# V0_8.net
KiCad netlist of a schematic drawn in EAGLE
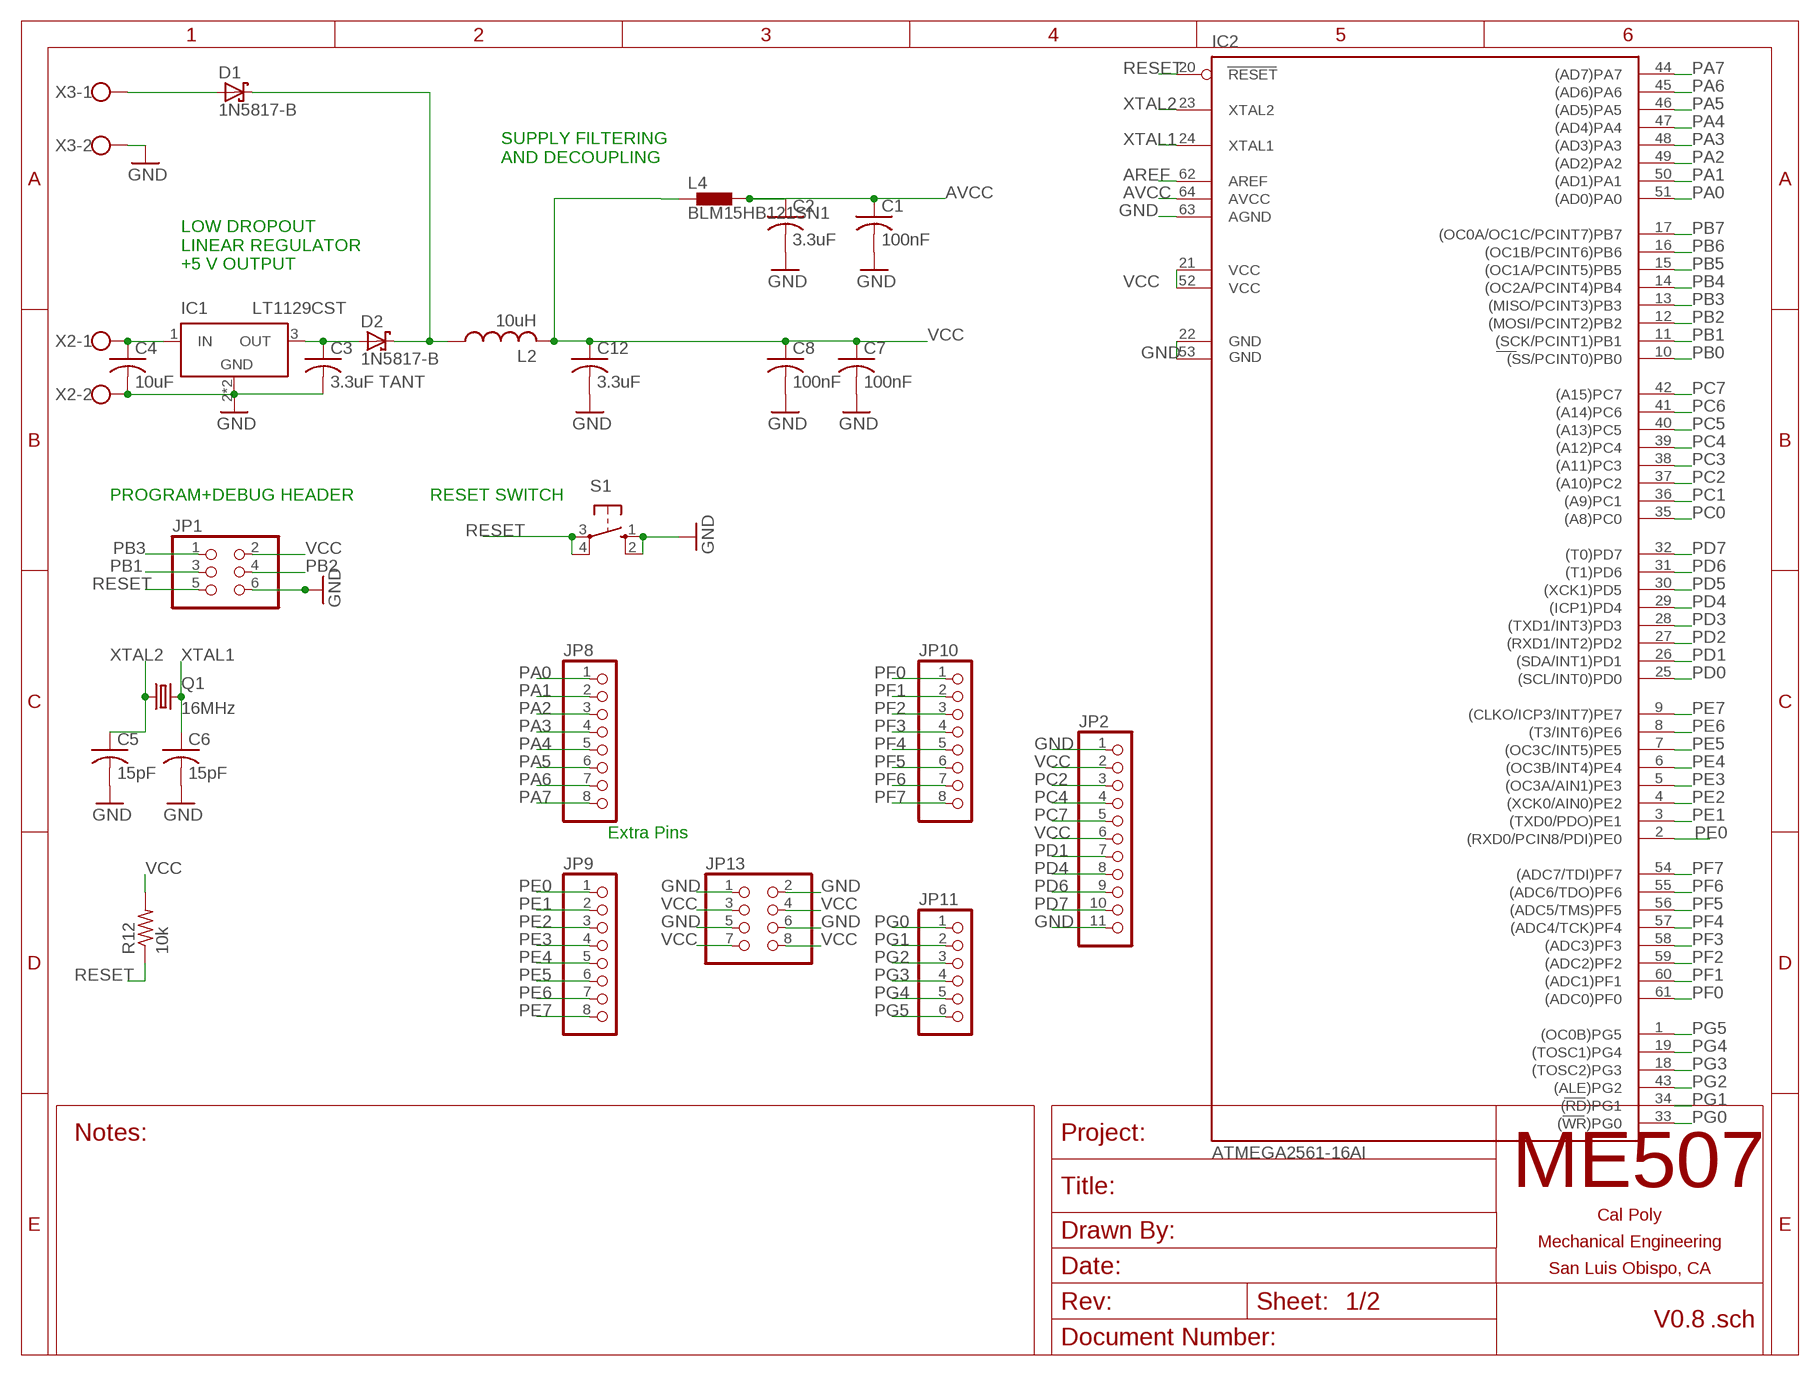
[diagram p0: schematic, sheet 1]
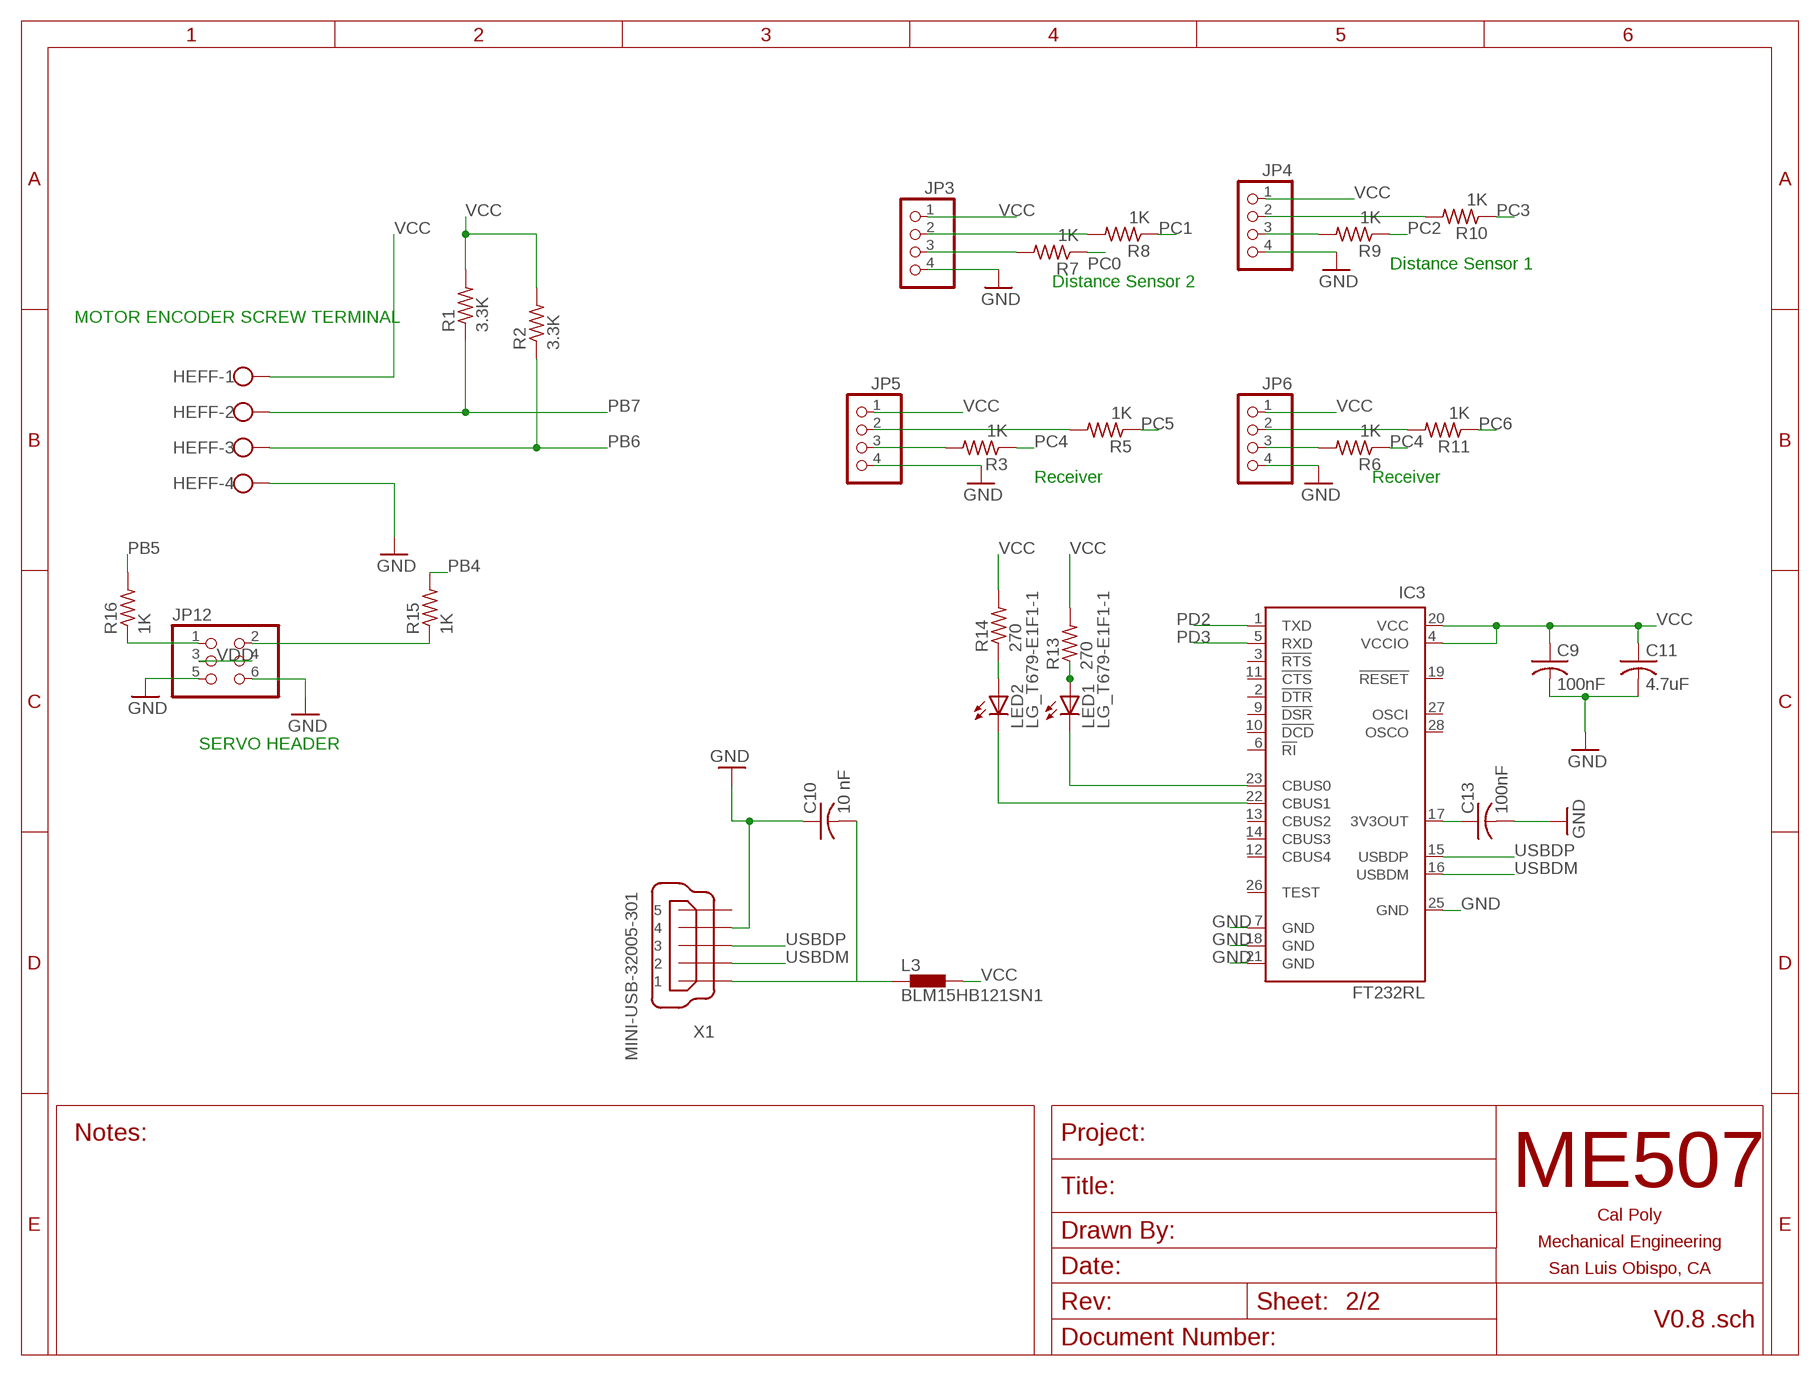
[diagram p1: schematic, sheet 2]

(export (version "E")
  (design (tool "Eeschema 10.0.6"))
  (components
    (comp (ref "C9")
      (value "100nF")
      (footprint "eagle-import:C0805")
      (libsource (lib "eagle-import") (part "C-USC0805"))
    )
    (comp (ref "C10")
      (value "10 nF")
      (footprint "eagle-import:C0805")
      (libsource (lib "eagle-import") (part "C-USC0805"))
    )
    (comp (ref "C11")
      (value "4.7uF")
      (footprint "eagle-import:C0805")
      (libsource (lib "eagle-import") (part "C-USC0805"))
    )
    (comp (ref "C13")
      (value "100nF")
      (footprint "eagle-import:C0805")
      (libsource (lib "eagle-import") (part "C-USC0805"))
    )
    (comp (ref "HEFF")
      (value "W237-4")
      (footprint "eagle-import:W237-4")
      (libsource (lib "eagle-import") (part "W237-4"))
    )
    (comp (ref "IC3")
      (value "FT232RL")
      (footprint "eagle-import:SSOP28")
      (libsource (lib "eagle-import") (part "FT232RL"))
    )
    (comp (ref "JP3")
      (value "PINHD-1X4")
      (footprint "eagle-import:1X04")
      (libsource (lib "eagle-import") (part "PINHD-1X4"))
    )
    (comp (ref "JP4")
      (value "PINHD-1X4")
      (footprint "eagle-import:1X04")
      (libsource (lib "eagle-import") (part "PINHD-1X4"))
    )
    (comp (ref "JP5")
      (value "PINHD-1X4")
      (footprint "eagle-import:1X04")
      (libsource (lib "eagle-import") (part "PINHD-1X4"))
    )
    (comp (ref "JP6")
      (value "PINHD-1X4")
      (footprint "eagle-import:1X04")
      (libsource (lib "eagle-import") (part "PINHD-1X4"))
    )
    (comp (ref "JP12")
      (value "PINHD-2X3")
      (footprint "eagle-import:2X03")
      (libsource (lib "eagle-import") (part "PINHD-2X3"))
    )
    (comp (ref "L3")
      (value "BLM15HB121SN1")
      (footprint "eagle-import:0402")
      (libsource (lib "eagle-import") (part "BLM15HB121SN1"))
    )
    (comp (ref "LED1")
      (value "LG_T679-E1F1-1")
      (footprint "eagle-import:PLCC2")
      (libsource (lib "eagle-import") (part "_T679-?-1E1F1LG"))
    )
    (comp (ref "LED2")
      (value "LG_T679-E1F1-1")
      (footprint "eagle-import:PLCC2")
      (libsource (lib "eagle-import") (part "_T679-?-1E1F1LG"))
    )
    (comp (ref "R1")
      (value "3.3K")
      (footprint "eagle-import:R0805")
      (libsource (lib "eagle-import") (part "R-US_R0805"))
    )
    (comp (ref "R2")
      (value "3.3K")
      (footprint "eagle-import:R0805")
      (libsource (lib "eagle-import") (part "R-US_R0805"))
    )
    (comp (ref "R3")
      (value "1K")
      (footprint "eagle-import:R0805")
      (libsource (lib "eagle-import") (part "R-US_R0805"))
    )
    (comp (ref "R5")
      (value "1K")
      (footprint "eagle-import:R0805")
      (libsource (lib "eagle-import") (part "R-US_R0805"))
    )
    (comp (ref "R6")
      (value "1K")
      (footprint "eagle-import:R0805")
      (libsource (lib "eagle-import") (part "R-US_R0805"))
    )
    (comp (ref "R7")
      (value "1K")
      (footprint "eagle-import:R0805")
      (libsource (lib "eagle-import") (part "R-US_R0805"))
    )
    (comp (ref "R8")
      (value "1K")
      (footprint "eagle-import:R0805")
      (libsource (lib "eagle-import") (part "R-US_R0805"))
    )
    (comp (ref "R9")
      (value "1K")
      (footprint "eagle-import:R0805")
      (libsource (lib "eagle-import") (part "R-US_R0805"))
    )
    (comp (ref "R10")
      (value "1K")
      (footprint "eagle-import:R0805")
      (libsource (lib "eagle-import") (part "R-US_R0805"))
    )
    (comp (ref "R11")
      (value "1K")
      (footprint "eagle-import:R0805")
      (libsource (lib "eagle-import") (part "R-US_R0805"))
    )
    (comp (ref "R13")
      (value "270")
      (footprint "eagle-import:R0805")
      (libsource (lib "eagle-import") (part "R-US_R0805"))
    )
    (comp (ref "R14")
      (value "270")
      (footprint "eagle-import:R0805")
      (libsource (lib "eagle-import") (part "R-US_R0805"))
    )
    (comp (ref "R15")
      (value "1K")
      (footprint "eagle-import:R0805")
      (libsource (lib "eagle-import") (part "R-US_R0805"))
    )
    (comp (ref "R16")
      (value "1K")
      (footprint "eagle-import:R0805")
      (libsource (lib "eagle-import") (part "R-US_R0805"))
    )
    (comp (ref "X1")
      (value "MINI-USB-32005-301")
      (footprint "eagle-import:32005-301")
      (libsource (lib "eagle-import") (part "MINI-USB-32005-301"))
    )
    (comp (ref "C1")
      (value "100nF")
      (footprint "eagle-import:C0805")
      (libsource (lib "eagle-import") (part "C-USC0805"))
    )
    (comp (ref "C2")
      (value "3.3uF")
      (footprint "eagle-import:C0805")
      (libsource (lib "eagle-import") (part "C-USC0805"))
    )
    (comp (ref "C3")
      (value "3.3uF TANT")
      (footprint "eagle-import:C0805")
      (libsource (lib "eagle-import") (part "C-USC0805"))
    )
    (comp (ref "C4")
      (value "10uF")
      (footprint "eagle-import:C0805")
      (libsource (lib "eagle-import") (part "C-USC0805"))
    )
    (comp (ref "C5")
      (value "15pF")
      (footprint "eagle-import:C0805")
      (libsource (lib "eagle-import") (part "C-USC0805"))
    )
    (comp (ref "C6")
      (value "15pF")
      (footprint "eagle-import:C0805")
      (libsource (lib "eagle-import") (part "C-USC0805"))
    )
    (comp (ref "C7")
      (value "100nF")
      (footprint "eagle-import:C0805")
      (libsource (lib "eagle-import") (part "C-USC0805"))
    )
    (comp (ref "C8")
      (value "100nF")
      (footprint "eagle-import:C0805")
      (libsource (lib "eagle-import") (part "C-USC0805"))
    )
    (comp (ref "C12")
      (value "3.3uF")
      (footprint "eagle-import:C0805")
      (libsource (lib "eagle-import") (part "C-USC0805"))
    )
    (comp (ref "D1")
      (value "1N5817-B")
      (footprint "eagle-import:DO41-7.6")
      (libsource (lib "eagle-import") (part "1N5817-B"))
    )
    (comp (ref "D2")
      (value "1N5817-B")
      (footprint "eagle-import:DO41-7.6")
      (libsource (lib "eagle-import") (part "1N5817-B"))
    )
    (comp (ref "IC1")
      (value "LT1129CST")
      (footprint "eagle-import:SOT223")
      (fields (field (name "MPN") "LT1129CST-5#PBF"))
      (libsource (lib "eagle-import") (part "LT1129CST"))
    )
    (comp (ref "IC2")
      (value "ATMEGA2561-16AI")
      (footprint "eagle-import:TQFP64")
      (libsource (lib "eagle-import") (part "ATMEGA2561AI-16"))
    )
    (comp (ref "JP1")
      (value "PINHD-2X3")
      (footprint "eagle-import:2X03")
      (libsource (lib "eagle-import") (part "PINHD-2X3"))
    )
    (comp (ref "JP2")
      (value "PINHD-1X11")
      (footprint "eagle-import:1X11")
      (libsource (lib "eagle-import") (part "PINHD-1X11"))
    )
    (comp (ref "JP8")
      (value "PINHD-1X8")
      (footprint "eagle-import:1X08")
      (libsource (lib "eagle-import") (part "PINHD-1X8"))
    )
    (comp (ref "JP9")
      (value "PINHD-1X8")
      (footprint "eagle-import:1X08")
      (libsource (lib "eagle-import") (part "PINHD-1X8"))
    )
    (comp (ref "JP10")
      (value "PINHD-1X8")
      (footprint "eagle-import:1X08")
      (libsource (lib "eagle-import") (part "PINHD-1X8"))
    )
    (comp (ref "JP11")
      (value "PINHD-1X6")
      (footprint "eagle-import:1X06")
      (libsource (lib "eagle-import") (part "PINHD-1X6"))
    )
    (comp (ref "JP13")
      (value "PINHD-2X4")
      (footprint "eagle-import:2X04")
      (libsource (lib "eagle-import") (part "PINHD-2X4"))
    )
    (comp (ref "L2")
      (value "10uH")
      (footprint "eagle-import:L1812")
      (libsource (lib "eagle-import") (part "L-USL1812"))
    )
    (comp (ref "L4")
      (value "BLM15HB121SN1")
      (footprint "eagle-import:0402")
      (libsource (lib "eagle-import") (part "BLM15HB121SN1"))
    )
    (comp (ref "Q1")
      (value "16MHz")
      (footprint "eagle-import:HC49_S")
      (libsource (lib "eagle-import") (part "CRYSTALHC49S"))
    )
    (comp (ref "R12")
      (value "10k")
      (footprint "eagle-import:R0805")
      (libsource (lib "eagle-import") (part "R-US_R0805"))
    )
    (comp (ref "S1")
      (value "10-XX")
      (footprint "eagle-import:B3F-10XX")
      (fields (field (name "MPN") "B3F-1000"))
      (libsource (lib "eagle-import") (part "10-XX"))
    )
    (comp (ref "X2")
      (value "W237-102")
      (footprint "eagle-import:W237-102")
      (fields (field (name "MPN") "237-102"))
      (libsource (lib "eagle-import") (part "W237-102"))
    )
    (comp (ref "X3")
      (value "W237-102")
      (footprint "eagle-import:W237-102")
      (fields (field (name "MPN") "237-102"))
      (libsource (lib "eagle-import") (part "W237-102"))
    )
  )
  (nets
    (net (code "1") (name "AREF") (class "Default")
      (node (ref "IC2") (pin "62") (pinfunction "AREF_62") (pintype "bidirectional"))
    )
    (net (code "2") (name "AVCC") (class "Default")
      (node (ref "C1") (pin "1") (pinfunction "1_1") (pintype "passive"))
      (node (ref "C2") (pin "1") (pinfunction "1_1") (pintype "passive"))
      (node (ref "IC2") (pin "64") (pinfunction "AVCC_64") (pintype "power_in"))
      (node (ref "L4") (pin "2") (pinfunction "2_2") (pintype "passive"))
    )
    (net (code "3") (name "GND") (class "Default")
      (node (ref "C1") (pin "2") (pinfunction "2_2") (pintype "passive"))
      (node (ref "C10") (pin "1") (pinfunction "1_1") (pintype "passive"))
      (node (ref "C11") (pin "2") (pinfunction "2_2") (pintype "passive"))
      (node (ref "C12") (pin "2") (pinfunction "2_2") (pintype "passive"))
      (node (ref "C13") (pin "2") (pinfunction "2_2") (pintype "passive"))
      (node (ref "C2") (pin "2") (pinfunction "2_2") (pintype "passive"))
      (node (ref "C3") (pin "2") (pinfunction "2_2") (pintype "passive"))
      (node (ref "C4") (pin "2") (pinfunction "2_2") (pintype "passive"))
      (node (ref "C5") (pin "2") (pinfunction "2_2") (pintype "passive"))
      (node (ref "C6") (pin "2") (pinfunction "2_2") (pintype "passive"))
      (node (ref "C7") (pin "2") (pinfunction "2_2") (pintype "passive"))
      (node (ref "C8") (pin "2") (pinfunction "2_2") (pintype "passive"))
      (node (ref "C9") (pin "2") (pinfunction "2_2") (pintype "passive"))
      (node (ref "HEFF") (pin "4") (pinfunction "KL_4") (pintype "passive"))
      (node (ref "IC1") (pin "2") (pinfunction "GND_2") (pintype "bidirectional"))
      (node (ref "IC1") (pin "4") (pinfunction "GND_4") (pintype "bidirectional"))
      (node (ref "IC2") (pin "22") (pinfunction "GND_22") (pintype "power_in"))
      (node (ref "IC2") (pin "53") (pinfunction "GND1_53") (pintype "power_in"))
      (node (ref "IC2") (pin "63") (pinfunction "AGND_63") (pintype "power_in"))
      (node (ref "IC3") (pin "18") (pinfunction "GND_18") (pintype "power_in"))
      (node (ref "IC3") (pin "21") (pinfunction "GND_21") (pintype "power_in"))
      (node (ref "IC3") (pin "25") (pinfunction "GND_25") (pintype "power_in"))
      (node (ref "IC3") (pin "7") (pinfunction "GND_7") (pintype "power_in"))
      (node (ref "JP1") (pin "6") (pinfunction "6_6") (pintype "passive"))
      (node (ref "JP12") (pin "5") (pinfunction "5_5") (pintype "passive"))
      (node (ref "JP12") (pin "6") (pinfunction "6_6") (pintype "passive"))
      (node (ref "JP13") (pin "1") (pinfunction "1_1") (pintype "passive"))
      (node (ref "JP13") (pin "2") (pinfunction "2_2") (pintype "passive"))
      (node (ref "JP13") (pin "5") (pinfunction "5_5") (pintype "passive"))
      (node (ref "JP13") (pin "6") (pinfunction "6_6") (pintype "passive"))
      (node (ref "JP2") (pin "1") (pinfunction "1_1") (pintype "passive"))
      (node (ref "JP2") (pin "11") (pinfunction "11_11") (pintype "passive"))
      (node (ref "JP3") (pin "4") (pinfunction "4_4") (pintype "passive"))
      (node (ref "JP4") (pin "4") (pinfunction "4_4") (pintype "passive"))
      (node (ref "JP5") (pin "4") (pinfunction "4_4") (pintype "passive"))
      (node (ref "JP6") (pin "4") (pinfunction "4_4") (pintype "passive"))
      (node (ref "S1") (pin "1") (pinfunction "S_1") (pintype "passive"))
      (node (ref "S1") (pin "2") (pinfunction "S1_2") (pintype "passive"))
      (node (ref "X1") (pin "4") (pinfunction "4_4") (pintype "passive"))
      (node (ref "X2") (pin "2") (pinfunction "KL_2") (pintype "passive"))
      (node (ref "X3") (pin "2") (pinfunction "KL_2") (pintype "passive"))
    )
    (net (code "4") (name "Net-(C10-Pad2)") (class "Default")
      (node (ref "C10") (pin "2") (pinfunction "2_2") (pintype "passive"))
      (node (ref "L3") (pin "1") (pinfunction "1_1") (pintype "passive"))
      (node (ref "X1") (pin "1") (pinfunction "1_1") (pintype "passive"))
    )
    (net (code "5") (name "Net-(D1-PadC)") (class "Default")
      (node (ref "D1") (pin "C") (pinfunction "C_C") (pintype "passive"))
      (node (ref "D2") (pin "C") (pinfunction "C_C") (pintype "passive"))
      (node (ref "L2") (pin "1") (pinfunction "1_1") (pintype "passive"))
    )
    (net (code "6") (name "Net-(IC1-IN)") (class "Default")
      (node (ref "C4") (pin "1") (pinfunction "1_1") (pintype "passive"))
      (node (ref "IC1") (pin "1") (pinfunction "IN_1") (pintype "bidirectional"))
      (node (ref "X2") (pin "1") (pinfunction "KL_1") (pintype "passive"))
    )
    (net (code "7") (name "Net-(IC1-OUT)") (class "Default")
      (node (ref "C3") (pin "1") (pinfunction "1_1") (pintype "passive"))
      (node (ref "D2") (pin "A") (pinfunction "A_A") (pintype "passive"))
      (node (ref "IC1") (pin "3") (pinfunction "OUT_3") (pintype "bidirectional"))
    )
    (net (code "8") (name "Net-(IC3-3V3OUT)") (class "Default")
      (node (ref "C13") (pin "1") (pinfunction "1_1") (pintype "passive"))
      (node (ref "IC3") (pin "17") (pinfunction "3V3OUT_17") (pintype "output"))
    )
    (net (code "9") (name "Net-(IC3-CBUS0)") (class "Default")
      (node (ref "IC3") (pin "23") (pinfunction "CBUS0_23") (pintype "bidirectional"))
      (node (ref "LED1") (pin "C") (pinfunction "C_C") (pintype "passive"))
    )
    (net (code "10") (name "Net-(IC3-CBUS1)") (class "Default")
      (node (ref "IC3") (pin "22") (pinfunction "CBUS1_22") (pintype "bidirectional"))
      (node (ref "LED2") (pin "C") (pinfunction "C_C") (pintype "passive"))
    )
    (net (code "11") (name "Net-(JP3-Pad2)") (class "Default")
      (node (ref "JP3") (pin "2") (pinfunction "2_2") (pintype "passive"))
      (node (ref "R8") (pin "2") (pinfunction "2_2") (pintype "passive"))
    )
    (net (code "12") (name "Net-(JP3-Pad3)") (class "Default")
      (node (ref "JP3") (pin "3") (pinfunction "3_3") (pintype "passive"))
      (node (ref "R7") (pin "2") (pinfunction "2_2") (pintype "passive"))
    )
    (net (code "13") (name "Net-(JP4-Pad2)") (class "Default")
      (node (ref "JP4") (pin "2") (pinfunction "2_2") (pintype "passive"))
      (node (ref "R10") (pin "2") (pinfunction "2_2") (pintype "passive"))
    )
    (net (code "14") (name "Net-(JP4-Pad3)") (class "Default")
      (node (ref "JP4") (pin "3") (pinfunction "3_3") (pintype "passive"))
      (node (ref "R9") (pin "2") (pinfunction "2_2") (pintype "passive"))
    )
    (net (code "15") (name "Net-(JP5-Pad2)") (class "Default")
      (node (ref "JP5") (pin "2") (pinfunction "2_2") (pintype "passive"))
      (node (ref "R5") (pin "2") (pinfunction "2_2") (pintype "passive"))
    )
    (net (code "16") (name "Net-(JP5-Pad3)") (class "Default")
      (node (ref "JP5") (pin "3") (pinfunction "3_3") (pintype "passive"))
      (node (ref "R3") (pin "2") (pinfunction "2_2") (pintype "passive"))
    )
    (net (code "17") (name "Net-(JP6-Pad2)") (class "Default")
      (node (ref "JP6") (pin "2") (pinfunction "2_2") (pintype "passive"))
      (node (ref "R11") (pin "2") (pinfunction "2_2") (pintype "passive"))
    )
    (net (code "18") (name "Net-(JP6-Pad3)") (class "Default")
      (node (ref "JP6") (pin "3") (pinfunction "3_3") (pintype "passive"))
      (node (ref "R6") (pin "2") (pinfunction "2_2") (pintype "passive"))
    )
    (net (code "19") (name "Net-(JP12-Pad1)") (class "Default")
      (node (ref "JP12") (pin "1") (pinfunction "1_1") (pintype "passive"))
      (node (ref "R16") (pin "1") (pinfunction "1_1") (pintype "passive"))
    )
    (net (code "20") (name "Net-(JP12-Pad2)") (class "Default")
      (node (ref "JP12") (pin "2") (pinfunction "2_2") (pintype "passive"))
      (node (ref "R15") (pin "1") (pinfunction "1_1") (pintype "passive"))
    )
    (net (code "21") (name "Net-(LED1-PadA)") (class "Default")
      (node (ref "LED1") (pin "A") (pinfunction "A_A") (pintype "passive"))
      (node (ref "R13") (pin "1") (pinfunction "1_1") (pintype "passive"))
    )
    (net (code "22") (name "Net-(LED2-PadA)") (class "Default")
      (node (ref "LED2") (pin "A") (pinfunction "A_A") (pintype "passive"))
      (node (ref "R14") (pin "1") (pinfunction "1_1") (pintype "passive"))
    )
    (net (code "23") (name "Net-(X3A-KL)") (class "Default")
      (node (ref "D1") (pin "A") (pinfunction "A_A") (pintype "passive"))
      (node (ref "X3") (pin "1") (pinfunction "KL_1") (pintype "passive"))
    )
    (net (code "24") (name "PA0") (class "Default")
      (node (ref "IC2") (pin "51") (pinfunction "(AD0)PA0_51") (pintype "bidirectional"))
      (node (ref "JP8") (pin "1") (pinfunction "1_1") (pintype "passive"))
    )
    (net (code "25") (name "PA1") (class "Default")
      (node (ref "IC2") (pin "50") (pinfunction "(AD1)PA1_50") (pintype "bidirectional"))
      (node (ref "JP8") (pin "2") (pinfunction "2_2") (pintype "passive"))
    )
    (net (code "26") (name "PA2") (class "Default")
      (node (ref "IC2") (pin "49") (pinfunction "(AD2)PA2_49") (pintype "bidirectional"))
      (node (ref "JP8") (pin "3") (pinfunction "3_3") (pintype "passive"))
    )
    (net (code "27") (name "PA3") (class "Default")
      (node (ref "IC2") (pin "48") (pinfunction "(AD3)PA3_48") (pintype "bidirectional"))
      (node (ref "JP8") (pin "4") (pinfunction "4_4") (pintype "passive"))
    )
    (net (code "28") (name "PA4") (class "Default")
      (node (ref "IC2") (pin "47") (pinfunction "(AD4)PA4_47") (pintype "bidirectional"))
      (node (ref "JP8") (pin "5") (pinfunction "5_5") (pintype "passive"))
    )
    (net (code "29") (name "PA5") (class "Default")
      (node (ref "IC2") (pin "46") (pinfunction "(AD5)PA5_46") (pintype "bidirectional"))
      (node (ref "JP8") (pin "6") (pinfunction "6_6") (pintype "passive"))
    )
    (net (code "30") (name "PA6") (class "Default")
      (node (ref "IC2") (pin "45") (pinfunction "(AD6)PA6_45") (pintype "bidirectional"))
      (node (ref "JP8") (pin "7") (pinfunction "7_7") (pintype "passive"))
    )
    (net (code "31") (name "PA7") (class "Default")
      (node (ref "IC2") (pin "44") (pinfunction "(AD7)PA7_44") (pintype "bidirectional"))
      (node (ref "JP8") (pin "8") (pinfunction "8_8") (pintype "passive"))
    )
    (net (code "32") (name "PB0") (class "Default")
      (node (ref "IC2") (pin "10") (pinfunction "(SS/PCINT0)PB0_10") (pintype "bidirectional"))
    )
    (net (code "33") (name "PB1") (class "Default")
      (node (ref "IC2") (pin "11") (pinfunction "(SCK/PCINT1)PB1_11") (pintype "bidirectional"))
      (node (ref "JP1") (pin "3") (pinfunction "3_3") (pintype "passive"))
    )
    (net (code "34") (name "PB2") (class "Default")
      (node (ref "IC2") (pin "12") (pinfunction "(MOSI/PCINT2)PB2_12") (pintype "bidirectional"))
      (node (ref "JP1") (pin "4") (pinfunction "4_4") (pintype "passive"))
    )
    (net (code "35") (name "PB3") (class "Default")
      (node (ref "IC2") (pin "13") (pinfunction "(MISO/PCINT3)PB3_13") (pintype "bidirectional"))
      (node (ref "JP1") (pin "1") (pinfunction "1_1") (pintype "passive"))
    )
    (net (code "36") (name "PB4") (class "Default")
      (node (ref "IC2") (pin "14") (pinfunction "(OC2A/PCINT4)PB4_14") (pintype "bidirectional"))
      (node (ref "R15") (pin "2") (pinfunction "2_2") (pintype "passive"))
    )
    (net (code "37") (name "PB5") (class "Default")
      (node (ref "IC2") (pin "15") (pinfunction "(OC1A/PCINT5)PB5_15") (pintype "bidirectional"))
      (node (ref "R16") (pin "2") (pinfunction "2_2") (pintype "passive"))
    )
    (net (code "38") (name "PB6") (class "Default")
      (node (ref "HEFF") (pin "3") (pinfunction "KL_3") (pintype "passive"))
      (node (ref "IC2") (pin "16") (pinfunction "(OC1B/PCINT6)PB6_16") (pintype "bidirectional"))
      (node (ref "R2") (pin "1") (pinfunction "1_1") (pintype "passive"))
    )
    (net (code "39") (name "PB7") (class "Default")
      (node (ref "HEFF") (pin "2") (pinfunction "KL_2") (pintype "passive"))
      (node (ref "IC2") (pin "17") (pinfunction "(OC0A/OC1C/PCINT7)PB7_17") (pintype "bidirectional"))
      (node (ref "R1") (pin "1") (pinfunction "1_1") (pintype "passive"))
    )
    (net (code "40") (name "PC0") (class "Default")
      (node (ref "IC2") (pin "35") (pinfunction "(A8)PC0_35") (pintype "bidirectional"))
      (node (ref "R7") (pin "1") (pinfunction "1_1") (pintype "passive"))
    )
    (net (code "41") (name "PC1") (class "Default")
      (node (ref "IC2") (pin "36") (pinfunction "(A9)PC1_36") (pintype "bidirectional"))
      (node (ref "R8") (pin "1") (pinfunction "1_1") (pintype "passive"))
    )
    (net (code "42") (name "PC2") (class "Default")
      (node (ref "IC2") (pin "37") (pinfunction "(A10)PC2_37") (pintype "bidirectional"))
      (node (ref "JP2") (pin "3") (pinfunction "3_3") (pintype "passive"))
      (node (ref "R9") (pin "1") (pinfunction "1_1") (pintype "passive"))
    )
    (net (code "43") (name "PC3") (class "Default")
      (node (ref "IC2") (pin "38") (pinfunction "(A11)PC3_38") (pintype "bidirectional"))
      (node (ref "R10") (pin "1") (pinfunction "1_1") (pintype "passive"))
    )
    (net (code "44") (name "PC4") (class "Default")
      (node (ref "IC2") (pin "39") (pinfunction "(A12)PC4_39") (pintype "bidirectional"))
      (node (ref "JP2") (pin "4") (pinfunction "4_4") (pintype "passive"))
      (node (ref "R3") (pin "1") (pinfunction "1_1") (pintype "passive"))
      (node (ref "R6") (pin "1") (pinfunction "1_1") (pintype "passive"))
    )
    (net (code "45") (name "PC5") (class "Default")
      (node (ref "IC2") (pin "40") (pinfunction "(A13)PC5_40") (pintype "bidirectional"))
      (node (ref "R5") (pin "1") (pinfunction "1_1") (pintype "passive"))
    )
    (net (code "46") (name "PC6") (class "Default")
      (node (ref "IC2") (pin "41") (pinfunction "(A14)PC6_41") (pintype "bidirectional"))
      (node (ref "R11") (pin "1") (pinfunction "1_1") (pintype "passive"))
    )
    (net (code "47") (name "PC7") (class "Default")
      (node (ref "IC2") (pin "42") (pinfunction "(A15)PC7_42") (pintype "bidirectional"))
      (node (ref "JP2") (pin "5") (pinfunction "5_5") (pintype "passive"))
    )
    (net (code "48") (name "PD0") (class "Default")
      (node (ref "IC2") (pin "25") (pinfunction "(SCL/INT0)PD0_25") (pintype "bidirectional"))
    )
    (net (code "49") (name "PD1") (class "Default")
      (node (ref "IC2") (pin "26") (pinfunction "(SDA/INT1)PD1_26") (pintype "bidirectional"))
      (node (ref "JP2") (pin "7") (pinfunction "7_7") (pintype "passive"))
    )
    (net (code "50") (name "PD2") (class "Default")
      (node (ref "IC2") (pin "27") (pinfunction "(RXD1/INT2)PD2_27") (pintype "bidirectional"))
      (node (ref "IC3") (pin "1") (pinfunction "TXD_1") (pintype "output"))
    )
    (net (code "51") (name "PD3") (class "Default")
      (node (ref "IC2") (pin "28") (pinfunction "(TXD1/INT3)PD3_28") (pintype "bidirectional"))
      (node (ref "IC3") (pin "5") (pinfunction "RXD_5") (pintype "input"))
    )
    (net (code "52") (name "PD4") (class "Default")
      (node (ref "IC2") (pin "29") (pinfunction "(ICP1)PD4_29") (pintype "bidirectional"))
      (node (ref "JP2") (pin "8") (pinfunction "8_8") (pintype "passive"))
    )
    (net (code "53") (name "PD5") (class "Default")
      (node (ref "IC2") (pin "30") (pinfunction "(XCK1)PD5_30") (pintype "bidirectional"))
    )
    (net (code "54") (name "PD6") (class "Default")
      (node (ref "IC2") (pin "31") (pinfunction "(T1)PD6_31") (pintype "bidirectional"))
      (node (ref "JP2") (pin "9") (pinfunction "9_9") (pintype "passive"))
    )
    (net (code "55") (name "PD7") (class "Default")
      (node (ref "IC2") (pin "32") (pinfunction "(T0)PD7_32") (pintype "bidirectional"))
      (node (ref "JP2") (pin "10") (pinfunction "10_10") (pintype "passive"))
    )
    (net (code "56") (name "PE0") (class "Default")
      (node (ref "IC2") (pin "2") (pinfunction "(RXD0/PCIN8/PDI)PE0_2") (pintype "bidirectional"))
      (node (ref "JP9") (pin "1") (pinfunction "1_1") (pintype "passive"))
    )
    (net (code "57") (name "PE1") (class "Default")
      (node (ref "IC2") (pin "3") (pinfunction "(TXD0/PDO)PE1_3") (pintype "bidirectional"))
      (node (ref "JP9") (pin "2") (pinfunction "2_2") (pintype "passive"))
    )
    (net (code "58") (name "PE2") (class "Default")
      (node (ref "IC2") (pin "4") (pinfunction "(XCK0/AIN0)PE2_4") (pintype "bidirectional"))
      (node (ref "JP9") (pin "3") (pinfunction "3_3") (pintype "passive"))
    )
    (net (code "59") (name "PE3") (class "Default")
      (node (ref "IC2") (pin "5") (pinfunction "(OC3A/AIN1)PE3_5") (pintype "bidirectional"))
      (node (ref "JP9") (pin "4") (pinfunction "4_4") (pintype "passive"))
    )
    (net (code "60") (name "PE4") (class "Default")
      (node (ref "IC2") (pin "6") (pinfunction "(OC3B/INT4)PE4_6") (pintype "bidirectional"))
      (node (ref "JP9") (pin "5") (pinfunction "5_5") (pintype "passive"))
    )
    (net (code "61") (name "PE5") (class "Default")
      (node (ref "IC2") (pin "7") (pinfunction "(OC3C/INT5)PE5_7") (pintype "bidirectional"))
      (node (ref "JP9") (pin "6") (pinfunction "6_6") (pintype "passive"))
    )
    (net (code "62") (name "PE6") (class "Default")
      (node (ref "IC2") (pin "8") (pinfunction "(T3/INT6)PE6_8") (pintype "bidirectional"))
      (node (ref "JP9") (pin "7") (pinfunction "7_7") (pintype "passive"))
    )
    (net (code "63") (name "PE7") (class "Default")
      (node (ref "IC2") (pin "9") (pinfunction "(CLKO/ICP3/INT7)PE7_9") (pintype "bidirectional"))
      (node (ref "JP9") (pin "8") (pinfunction "8_8") (pintype "passive"))
    )
    (net (code "64") (name "PF0") (class "Default")
      (node (ref "IC2") (pin "61") (pinfunction "(ADC0)PF0_61") (pintype "bidirectional"))
      (node (ref "JP10") (pin "1") (pinfunction "1_1") (pintype "passive"))
    )
    (net (code "65") (name "PF1") (class "Default")
      (node (ref "IC2") (pin "60") (pinfunction "(ADC1)PF1_60") (pintype "bidirectional"))
      (node (ref "JP10") (pin "2") (pinfunction "2_2") (pintype "passive"))
    )
    (net (code "66") (name "PF2") (class "Default")
      (node (ref "IC2") (pin "59") (pinfunction "(ADC2)PF2_59") (pintype "bidirectional"))
      (node (ref "JP10") (pin "3") (pinfunction "3_3") (pintype "passive"))
    )
    (net (code "67") (name "PF3") (class "Default")
      (node (ref "IC2") (pin "58") (pinfunction "(ADC3)PF3_58") (pintype "bidirectional"))
      (node (ref "JP10") (pin "4") (pinfunction "4_4") (pintype "passive"))
    )
    (net (code "68") (name "PF4") (class "Default")
      (node (ref "IC2") (pin "57") (pinfunction "(ADC4/TCK)PF4_57") (pintype "bidirectional"))
      (node (ref "JP10") (pin "5") (pinfunction "5_5") (pintype "passive"))
    )
    (net (code "69") (name "PF5") (class "Default")
      (node (ref "IC2") (pin "56") (pinfunction "(ADC5/TMS)PF5_56") (pintype "bidirectional"))
      (node (ref "JP10") (pin "6") (pinfunction "6_6") (pintype "passive"))
    )
    (net (code "70") (name "PF6") (class "Default")
      (node (ref "IC2") (pin "55") (pinfunction "(ADC6/TDO)PF6_55") (pintype "bidirectional"))
      (node (ref "JP10") (pin "7") (pinfunction "7_7") (pintype "passive"))
    )
    (net (code "71") (name "PF7") (class "Default")
      (node (ref "IC2") (pin "54") (pinfunction "(ADC7/TDI)PF7_54") (pintype "bidirectional"))
      (node (ref "JP10") (pin "8") (pinfunction "8_8") (pintype "passive"))
    )
    (net (code "72") (name "PG0") (class "Default")
      (node (ref "IC2") (pin "33") (pinfunction "(WR)PG0_33") (pintype "bidirectional"))
      (node (ref "JP11") (pin "1") (pinfunction "1_1") (pintype "passive"))
    )
    (net (code "73") (name "PG1") (class "Default")
      (node (ref "IC2") (pin "34") (pinfunction "(RD)PG1_34") (pintype "bidirectional"))
      (node (ref "JP11") (pin "2") (pinfunction "2_2") (pintype "passive"))
    )
    (net (code "74") (name "PG2") (class "Default")
      (node (ref "IC2") (pin "43") (pinfunction "(ALE)PG2_43") (pintype "bidirectional"))
      (node (ref "JP11") (pin "3") (pinfunction "3_3") (pintype "passive"))
    )
    (net (code "75") (name "PG3") (class "Default")
      (node (ref "IC2") (pin "18") (pinfunction "(TOSC2)PG3_18") (pintype "bidirectional"))
      (node (ref "JP11") (pin "4") (pinfunction "4_4") (pintype "passive"))
    )
    (net (code "76") (name "PG4") (class "Default")
      (node (ref "IC2") (pin "19") (pinfunction "(TOSC1)PG4_19") (pintype "bidirectional"))
      (node (ref "JP11") (pin "5") (pinfunction "5_5") (pintype "passive"))
    )
    (net (code "77") (name "PG5") (class "Default")
      (node (ref "IC2") (pin "1") (pinfunction "(OC0B)PG5_1") (pintype "bidirectional"))
      (node (ref "JP11") (pin "6") (pinfunction "6_6") (pintype "passive"))
    )
    (net (code "78") (name "RESET") (class "Default")
      (node (ref "IC2") (pin "20") (pinfunction "RESET_20") (pintype "input"))
      (node (ref "JP1") (pin "5") (pinfunction "5_5") (pintype "passive"))
      (node (ref "R12") (pin "1") (pinfunction "1_1") (pintype "passive"))
      (node (ref "S1") (pin "3") (pinfunction "P_3") (pintype "passive"))
      (node (ref "S1") (pin "4") (pinfunction "P1_4") (pintype "passive"))
    )
    (net (code "79") (name "USBDM") (class "Default")
      (node (ref "IC3") (pin "16") (pinfunction "USBDM_16") (pintype "bidirectional"))
      (node (ref "X1") (pin "2") (pinfunction "2_2") (pintype "passive"))
    )
    (net (code "80") (name "USBDP") (class "Default")
      (node (ref "IC3") (pin "15") (pinfunction "USBDP_15") (pintype "bidirectional"))
      (node (ref "X1") (pin "3") (pinfunction "3_3") (pintype "passive"))
    )
    (net (code "81") (name "VCC") (class "Default")
      (node (ref "C11") (pin "1") (pinfunction "1_1") (pintype "passive"))
      (node (ref "C12") (pin "1") (pinfunction "1_1") (pintype "passive"))
      (node (ref "C7") (pin "1") (pinfunction "1_1") (pintype "passive"))
      (node (ref "C8") (pin "1") (pinfunction "1_1") (pintype "passive"))
      (node (ref "C9") (pin "1") (pinfunction "1_1") (pintype "passive"))
      (node (ref "HEFF") (pin "1") (pinfunction "KL_1") (pintype "passive"))
      (node (ref "IC2") (pin "21") (pinfunction "VCC_21") (pintype "power_in"))
      (node (ref "IC2") (pin "52") (pinfunction "VCC1_52") (pintype "power_in"))
      (node (ref "IC3") (pin "20") (pinfunction "VCC_20") (pintype "power_in"))
      (node (ref "IC3") (pin "4") (pinfunction "VCCIO_4") (pintype "power_in"))
      (node (ref "JP1") (pin "2") (pinfunction "2_2") (pintype "passive"))
      (node (ref "JP13") (pin "3") (pinfunction "3_3") (pintype "passive"))
      (node (ref "JP13") (pin "4") (pinfunction "4_4") (pintype "passive"))
      (node (ref "JP13") (pin "7") (pinfunction "7_7") (pintype "passive"))
      (node (ref "JP13") (pin "8") (pinfunction "8_8") (pintype "passive"))
      (node (ref "JP2") (pin "2") (pinfunction "2_2") (pintype "passive"))
      (node (ref "JP2") (pin "6") (pinfunction "6_6") (pintype "passive"))
      (node (ref "JP3") (pin "1") (pinfunction "1_1") (pintype "passive"))
      (node (ref "JP4") (pin "1") (pinfunction "1_1") (pintype "passive"))
      (node (ref "JP5") (pin "1") (pinfunction "1_1") (pintype "passive"))
      (node (ref "JP6") (pin "1") (pinfunction "1_1") (pintype "passive"))
      (node (ref "L2") (pin "2") (pinfunction "2_2") (pintype "passive"))
      (node (ref "L3") (pin "2") (pinfunction "2_2") (pintype "passive"))
      (node (ref "L4") (pin "1") (pinfunction "1_1") (pintype "passive"))
      (node (ref "R1") (pin "2") (pinfunction "2_2") (pintype "passive"))
      (node (ref "R12") (pin "2") (pinfunction "2_2") (pintype "passive"))
      (node (ref "R13") (pin "2") (pinfunction "2_2") (pintype "passive"))
      (node (ref "R14") (pin "2") (pinfunction "2_2") (pintype "passive"))
      (node (ref "R2") (pin "2") (pinfunction "2_2") (pintype "passive"))
    )
    (net (code "82") (name "VDD") (class "Default")
      (node (ref "JP12") (pin "3") (pinfunction "3_3") (pintype "passive"))
      (node (ref "JP12") (pin "4") (pinfunction "4_4") (pintype "passive"))
    )
    (net (code "83") (name "XTAL1") (class "Default")
      (node (ref "C6") (pin "1") (pinfunction "1_1") (pintype "passive"))
      (node (ref "IC2") (pin "24") (pinfunction "XTAL1_24") (pintype "input"))
      (node (ref "Q1") (pin "2") (pinfunction "2_2") (pintype "passive"))
    )
    (net (code "84") (name "XTAL2") (class "Default")
      (node (ref "C5") (pin "1") (pinfunction "1_1") (pintype "passive"))
      (node (ref "IC2") (pin "23") (pinfunction "XTAL2_23") (pintype "output"))
      (node (ref "Q1") (pin "1") (pinfunction "1_1") (pintype "passive"))
    )
    (net (code "85") (name "unconnected-(IC3-CBUS2-Pad13)") (class "Default")
      (node (ref "IC3") (pin "13") (pinfunction "CBUS2_13") (pintype "bidirectional"))
    )
    (net (code "86") (name "unconnected-(IC3-CBUS3-Pad14)") (class "Default")
      (node (ref "IC3") (pin "14") (pinfunction "CBUS3_14") (pintype "bidirectional"))
    )
    (net (code "87") (name "unconnected-(IC3-CBUS4-Pad12)") (class "Default")
      (node (ref "IC3") (pin "12") (pinfunction "CBUS4_12") (pintype "bidirectional"))
    )
    (net (code "88") (name "unconnected-(IC3-OSCI-Pad27)") (class "Default")
      (node (ref "IC3") (pin "27") (pinfunction "OSCI_27") (pintype "input"))
    )
    (net (code "89") (name "unconnected-(IC3-OSCO-Pad28)") (class "Default")
      (node (ref "IC3") (pin "28") (pinfunction "OSCO_28") (pintype "output"))
    )
    (net (code "90") (name "unconnected-(IC3-TEST-Pad26)") (class "Default")
      (node (ref "IC3") (pin "26") (pinfunction "TEST_26") (pintype "input"))
    )
    (net (code "91") (name "unconnected-(IC3-~{CTS}-Pad11)") (class "Default")
      (node (ref "IC3") (pin "11") (pinfunction "~{CTS}_11") (pintype "input"))
    )
    (net (code "92") (name "unconnected-(IC3-~{DCD}-Pad10)") (class "Default")
      (node (ref "IC3") (pin "10") (pinfunction "~{DCD}_10") (pintype "input"))
    )
    (net (code "93") (name "unconnected-(IC3-~{DSR}-Pad9)") (class "Default")
      (node (ref "IC3") (pin "9") (pinfunction "~{DSR}_9") (pintype "input"))
    )
    (net (code "94") (name "unconnected-(IC3-~{DTR}-Pad2)") (class "Default")
      (node (ref "IC3") (pin "2") (pinfunction "~{DTR}_2") (pintype "output"))
    )
    (net (code "95") (name "unconnected-(IC3-~{RESET}-Pad19)") (class "Default")
      (node (ref "IC3") (pin "19") (pinfunction "~{RESET}_19") (pintype "input"))
    )
    (net (code "96") (name "unconnected-(IC3-~{RI}-Pad6)") (class "Default")
      (node (ref "IC3") (pin "6") (pinfunction "~{RI}_6") (pintype "input"))
    )
    (net (code "97") (name "unconnected-(IC3-~{RTS}-Pad3)") (class "Default")
      (node (ref "IC3") (pin "3") (pinfunction "~{RTS}_3") (pintype "output"))
    )
    (net (code "98") (name "unconnected-(X1-Pad5)") (class "Default")
      (node (ref "X1") (pin "5") (pinfunction "5_5") (pintype "passive"))
    )
  )
)
